# 00_-_Top_Sheet.net
KiCad netlist of a schematic drawn in Altium Designer
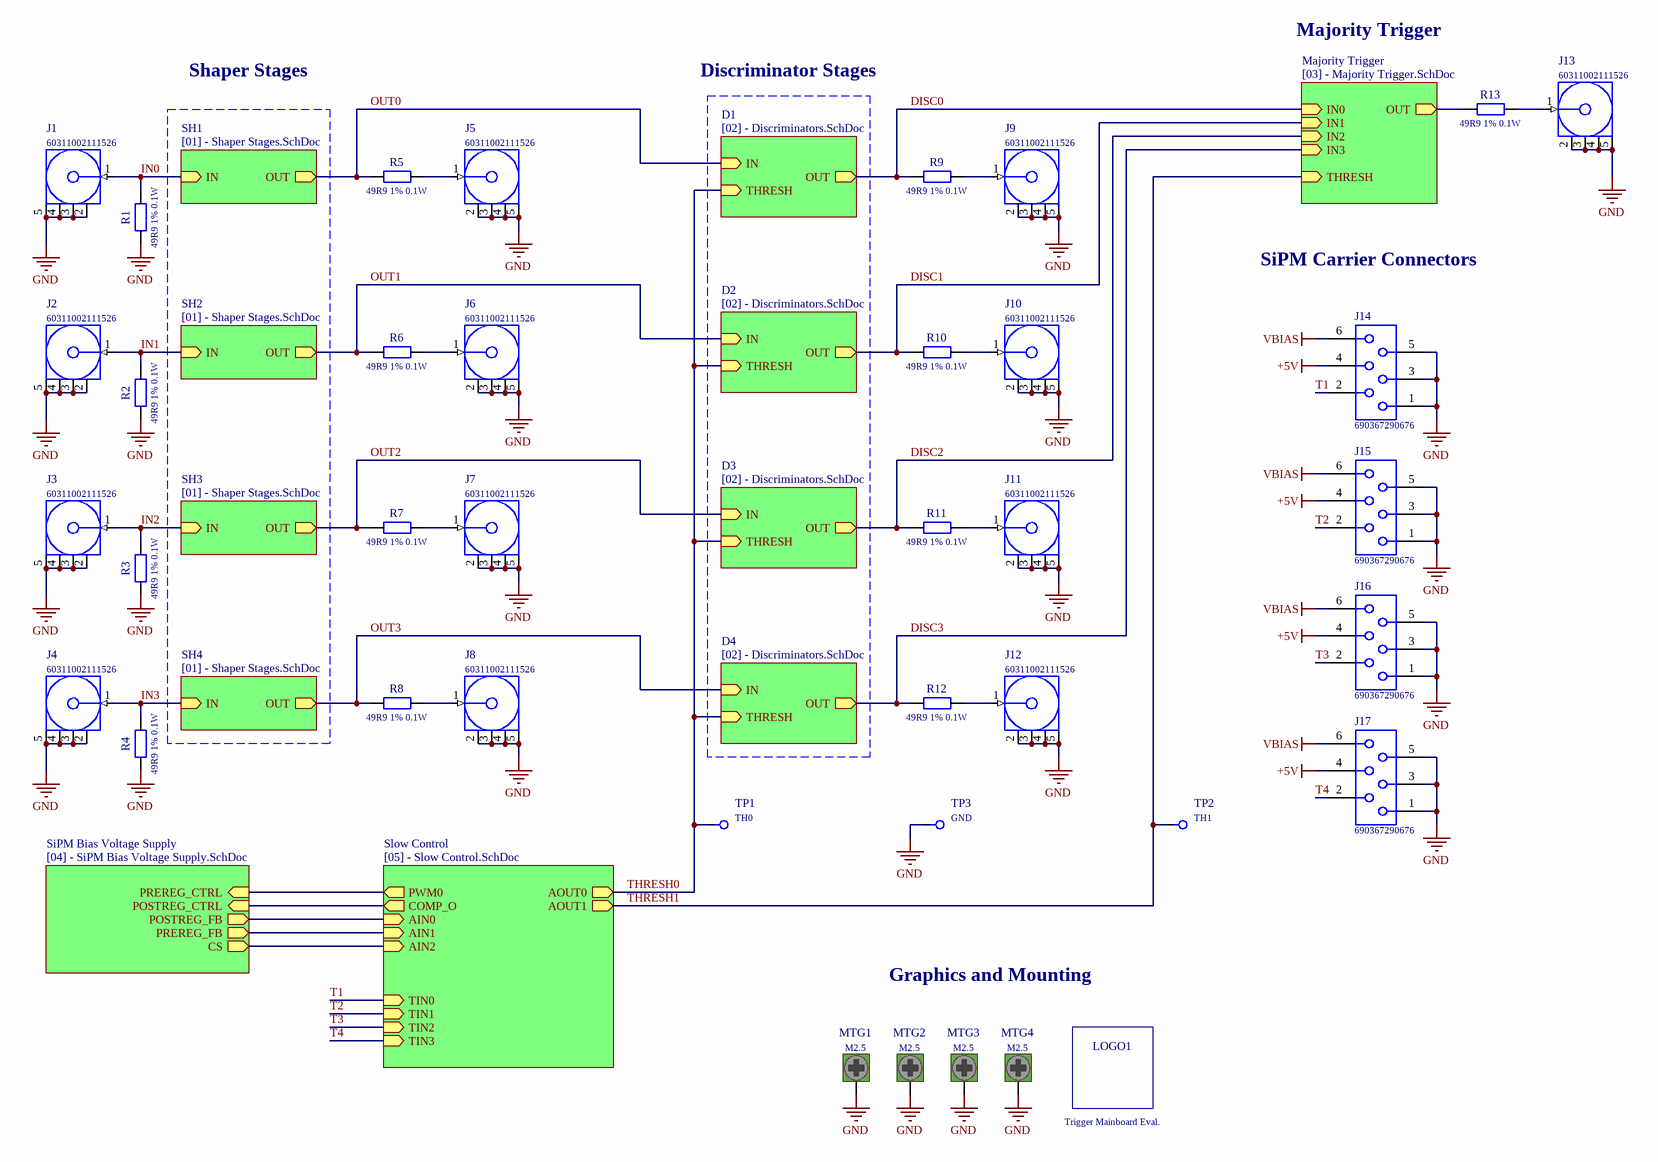
[diagram p0: [00] - Top Sheet.SchDoc]

(export (version "E")
  (design (tool "Eeschema 10.0.6"))
  (components
    (comp (ref "J1")
      (value "60311002111526")
      (footprint "60311002111526")
      (description "WR-SMA PCB Jack, THT, Right Angle")
      (fields (field (name "MANUFACTURER") "Wurth Elektronik"))
      (libsource (lib "WR-SMA") (part "60311002111526"))
    )
    (comp (ref "J2")
      (value "60311002111526")
      (footprint "60311002111526")
      (description "WR-SMA PCB Jack, THT, Right Angle")
      (fields (field (name "MANUFACTURER") "Wurth Elektronik"))
      (libsource (lib "WR-SMA") (part "60311002111526"))
    )
    (comp (ref "J3")
      (value "60311002111526")
      (footprint "60311002111526")
      (description "WR-SMA PCB Jack, THT, Right Angle")
      (fields (field (name "MANUFACTURER") "Wurth Elektronik"))
      (libsource (lib "WR-SMA") (part "60311002111526"))
    )
    (comp (ref "J4")
      (value "60311002111526")
      (footprint "60311002111526")
      (description "WR-SMA PCB Jack, THT, Right Angle")
      (fields (field (name "MANUFACTURER") "Wurth Elektronik"))
      (libsource (lib "WR-SMA") (part "60311002111526"))
    )
    (comp (ref "J5")
      (value "60311002111526")
      (footprint "60311002111526")
      (description "WR-SMA PCB Jack, THT, Right Angle")
      (fields (field (name "MANUFACTURER") "Wurth Elektronik"))
      (libsource (lib "WR-SMA") (part "60311002111526"))
    )
    (comp (ref "J6")
      (value "60311002111526")
      (footprint "60311002111526")
      (description "WR-SMA PCB Jack, THT, Right Angle")
      (fields (field (name "MANUFACTURER") "Wurth Elektronik"))
      (libsource (lib "WR-SMA") (part "60311002111526"))
    )
    (comp (ref "J7")
      (value "60311002111526")
      (footprint "60311002111526")
      (description "WR-SMA PCB Jack, THT, Right Angle")
      (fields (field (name "MANUFACTURER") "Wurth Elektronik"))
      (libsource (lib "WR-SMA") (part "60311002111526"))
    )
    (comp (ref "J8")
      (value "60311002111526")
      (footprint "60311002111526")
      (description "WR-SMA PCB Jack, THT, Right Angle")
      (fields (field (name "MANUFACTURER") "Wurth Elektronik"))
      (libsource (lib "WR-SMA") (part "60311002111526"))
    )
    (comp (ref "J9")
      (value "60311002111526")
      (footprint "60311002111526")
      (description "WR-SMA PCB Jack, THT, Right Angle")
      (fields (field (name "MANUFACTURER") "Wurth Elektronik"))
      (libsource (lib "WR-SMA") (part "60311002111526"))
    )
    (comp (ref "J10")
      (value "60311002111526")
      (footprint "60311002111526")
      (description "WR-SMA PCB Jack, THT, Right Angle")
      (fields (field (name "MANUFACTURER") "Wurth Elektronik"))
      (libsource (lib "WR-SMA") (part "60311002111526"))
    )
    (comp (ref "J11")
      (value "60311002111526")
      (footprint "60311002111526")
      (description "WR-SMA PCB Jack, THT, Right Angle")
      (fields (field (name "MANUFACTURER") "Wurth Elektronik"))
      (libsource (lib "WR-SMA") (part "60311002111526"))
    )
    (comp (ref "J12")
      (value "60311002111526")
      (footprint "60311002111526")
      (description "WR-SMA PCB Jack, THT, Right Angle")
      (fields (field (name "MANUFACTURER") "Wurth Elektronik"))
      (libsource (lib "WR-SMA") (part "60311002111526"))
    )
    (comp (ref "J13")
      (value "60311002111526")
      (footprint "60311002111526")
      (description "WR-SMA PCB Jack, THT, Right Angle")
      (fields (field (name "MANUFACTURER") "Wurth Elektronik"))
      (libsource (lib "WR-SMA") (part "60311002111526"))
    )
    (comp (ref "J14")
      (value "690367290676")
      (footprint "690367290676")
      (description "WR-MM MiniModule Connector, Female, SMT, Vertical, pitch 2.54mm, 6pins")
      (fields (field (name "MANUFACTURER") "Wurth Elektronik"))
      (libsource (lib "WR-MM") (part "690367290676"))
    )
    (comp (ref "J15")
      (value "690367290676")
      (footprint "690367290676")
      (description "WR-MM MiniModule Connector, Female, SMT, Vertical, pitch 2.54mm, 6pins")
      (fields (field (name "MANUFACTURER") "Wurth Elektronik"))
      (libsource (lib "WR-MM") (part "690367290676"))
    )
    (comp (ref "J16")
      (value "690367290676")
      (footprint "690367290676")
      (description "WR-MM MiniModule Connector, Female, SMT, Vertical, pitch 2.54mm, 6pins")
      (fields (field (name "MANUFACTURER") "Wurth Elektronik"))
      (libsource (lib "WR-MM") (part "690367290676"))
    )
    (comp (ref "J17")
      (value "690367290676")
      (footprint "690367290676")
      (description "WR-MM MiniModule Connector, Female, SMT, Vertical, pitch 2.54mm, 6pins")
      (fields (field (name "MANUFACTURER") "Wurth Elektronik"))
      (libsource (lib "WR-MM") (part "690367290676"))
    )
    (comp (ref "LOGO1")
      (value "Trigger Mainboard Eval.")
      (footprint "RWTH_LOGO_4x15MM")
      (description "Logo Spaceholder.")
      (fields (field (name "MANUFACTURER") "RWTH"))
      (libsource (lib "CustomComponents") (part "Logo"))
    )
    (comp (ref "MTG1")
      (value "M2.5")
      (footprint "Mounting_Hole_M2.5")
      (description "Simple mounting hole.")
      (libsource (lib "CustomComponents") (part "Mounting_Hole"))
    )
    (comp (ref "MTG2")
      (value "M2.5")
      (footprint "Mounting_Hole_M2.5")
      (description "Simple mounting hole.")
      (libsource (lib "CustomComponents") (part "Mounting_Hole"))
    )
    (comp (ref "MTG3")
      (value "M2.5")
      (footprint "Mounting_Hole_M2.5")
      (description "Simple mounting hole.")
      (libsource (lib "CustomComponents") (part "Mounting_Hole"))
    )
    (comp (ref "MTG4")
      (value "M2.5")
      (footprint "Mounting_Hole_M2.5")
      (description "Simple mounting hole.")
      (libsource (lib "CustomComponents") (part "Mounting_Hole"))
    )
    (comp (ref "R1")
      (value "49R9 1% 0.1W")
      (footprint "0603_RES")
      (description "Simple generic resistor.")
      (libsource (lib "CustomComponents") (part "Resistor"))
    )
    (comp (ref "R2")
      (value "49R9 1% 0.1W")
      (footprint "0603_RES")
      (description "Simple generic resistor.")
      (libsource (lib "CustomComponents") (part "Resistor"))
    )
    (comp (ref "R3")
      (value "49R9 1% 0.1W")
      (footprint "0603_RES")
      (description "Simple generic resistor.")
      (libsource (lib "CustomComponents") (part "Resistor"))
    )
    (comp (ref "R4")
      (value "49R9 1% 0.1W")
      (footprint "0603_RES")
      (description "Simple generic resistor.")
      (libsource (lib "CustomComponents") (part "Resistor"))
    )
    (comp (ref "R5")
      (value "49R9 1% 0.1W")
      (footprint "0603_RES")
      (description "Simple generic resistor.")
      (libsource (lib "CustomComponents") (part "Resistor"))
    )
    (comp (ref "R6")
      (value "49R9 1% 0.1W")
      (footprint "0603_RES")
      (description "Simple generic resistor.")
      (libsource (lib "CustomComponents") (part "Resistor"))
    )
    (comp (ref "R7")
      (value "49R9 1% 0.1W")
      (footprint "0603_RES")
      (description "Simple generic resistor.")
      (libsource (lib "CustomComponents") (part "Resistor"))
    )
    (comp (ref "R8")
      (value "49R9 1% 0.1W")
      (footprint "0603_RES")
      (description "Simple generic resistor.")
      (libsource (lib "CustomComponents") (part "Resistor"))
    )
    (comp (ref "R9")
      (value "49R9 1% 0.1W")
      (footprint "0603_RES")
      (description "Simple generic resistor.")
      (libsource (lib "CustomComponents") (part "Resistor"))
    )
    (comp (ref "R10")
      (value "49R9 1% 0.1W")
      (footprint "0603_RES")
      (description "Simple generic resistor.")
      (libsource (lib "CustomComponents") (part "Resistor"))
    )
    (comp (ref "R11")
      (value "49R9 1% 0.1W")
      (footprint "0603_RES")
      (description "Simple generic resistor.")
      (libsource (lib "CustomComponents") (part "Resistor"))
    )
    (comp (ref "R12")
      (value "49R9 1% 0.1W")
      (footprint "0603_RES")
      (description "Simple generic resistor.")
      (libsource (lib "CustomComponents") (part "Resistor"))
    )
    (comp (ref "R13")
      (value "49R9 1% 0.1W")
      (footprint "0603_RES")
      (description "Simple generic resistor.")
      (libsource (lib "CustomComponents") (part "Resistor"))
    )
    (comp (ref "TP1")
      (value "TH0")
      (footprint "Testpoint_5002")
      (fields (field (name "MANUFACTURER") "Keystone Electronics") (field (name "PARTNUMBER") "500X"))
      (libsource (lib "CustomComponents") (part "Testpoint"))
    )
    (comp (ref "TP2")
      (value "TH1")
      (footprint "Testpoint_5002")
      (fields (field (name "MANUFACTURER") "Keystone Electronics") (field (name "PARTNUMBER") "500X"))
      (libsource (lib "CustomComponents") (part "Testpoint"))
    )
    (comp (ref "TP3")
      (value "GND")
      (footprint "Testpoint_5001")
      (fields (field (name "MANUFACTURER") "Keystone Electronics") (field (name "PARTNUMBER") "500X"))
      (libsource (lib "CustomComponents") (part "Testpoint"))
    )
  )
  (nets
    (net (code "1") (name "+5V") (class "Default")
      (node (ref "J14") (pin "4") (pinfunction "4_4") (pintype "passive"))
      (node (ref "J15") (pin "4") (pinfunction "4_4") (pintype "passive"))
      (node (ref "J16") (pin "4") (pinfunction "4_4") (pintype "passive"))
      (node (ref "J17") (pin "4") (pinfunction "4_4") (pintype "passive"))
    )
    (net (code "4") (name "/DISC0") (class "Default")
      (node (ref "R9") (pin "2") (pinfunction "2_2") (pintype "passive"))
    )
    (net (code "5") (name "/DISC1") (class "Default")
      (node (ref "R10") (pin "2") (pinfunction "2_2") (pintype "passive"))
    )
    (net (code "6") (name "/DISC2") (class "Default")
      (node (ref "R11") (pin "2") (pinfunction "2_2") (pintype "passive"))
    )
    (net (code "7") (name "/DISC3") (class "Default")
      (node (ref "R12") (pin "2") (pinfunction "2_2") (pintype "passive"))
    )
    (net (code "8") (name "/IN0") (class "Default")
      (node (ref "J1") (pin "1") (pinfunction "Signal_1") (pintype "input"))
      (node (ref "R1") (pin "1") (pinfunction "1_1") (pintype "passive"))
    )
    (net (code "9") (name "/IN1") (class "Default")
      (node (ref "J2") (pin "1") (pinfunction "Signal_1") (pintype "input"))
      (node (ref "R2") (pin "1") (pinfunction "1_1") (pintype "passive"))
    )
    (net (code "10") (name "/IN2") (class "Default")
      (node (ref "J3") (pin "1") (pinfunction "Signal_1") (pintype "input"))
      (node (ref "R3") (pin "1") (pinfunction "1_1") (pintype "passive"))
    )
    (net (code "11") (name "/IN3") (class "Default")
      (node (ref "J4") (pin "1") (pinfunction "Signal_1") (pintype "input"))
      (node (ref "R4") (pin "1") (pinfunction "1_1") (pintype "passive"))
    )
    (net (code "12") (name "/OUT") (class "Default")
      (node (ref "R13") (pin "2") (pinfunction "2_2") (pintype "passive"))
    )
    (net (code "13") (name "/OUT0") (class "Default")
      (node (ref "R5") (pin "2") (pinfunction "2_2") (pintype "passive"))
    )
    (net (code "14") (name "/OUT1") (class "Default")
      (node (ref "R6") (pin "2") (pinfunction "2_2") (pintype "passive"))
    )
    (net (code "15") (name "/OUT2") (class "Default")
      (node (ref "R7") (pin "2") (pinfunction "2_2") (pintype "passive"))
    )
    (net (code "16") (name "/OUT3") (class "Default")
      (node (ref "R8") (pin "2") (pinfunction "2_2") (pintype "passive"))
    )
    (net (code "20") (name "/T1") (class "Default")
      (node (ref "J14") (pin "2") (pinfunction "2_2") (pintype "passive"))
    )
    (net (code "21") (name "/T2") (class "Default")
      (node (ref "J15") (pin "2") (pinfunction "2_2") (pintype "passive"))
    )
    (net (code "22") (name "/T3") (class "Default")
      (node (ref "J16") (pin "2") (pinfunction "2_2") (pintype "passive"))
    )
    (net (code "23") (name "/T4") (class "Default")
      (node (ref "J17") (pin "2") (pinfunction "2_2") (pintype "passive"))
    )
    (net (code "24") (name "/THRESH0") (class "Default")
      (node (ref "TP1") (pin "1") (pinfunction "1_1") (pintype "passive"))
    )
    (net (code "25") (name "/THRESH1") (class "Default")
      (node (ref "TP2") (pin "1") (pinfunction "1_1") (pintype "passive"))
    )
    (net (code "26") (name "GND") (class "Default")
      (node (ref "J1") (pin "2") (pinfunction "GND_2") (pintype "power_in"))
      (node (ref "J1") (pin "3") (pinfunction "GND_3") (pintype "power_in"))
      (node (ref "J1") (pin "4") (pinfunction "GND_4") (pintype "power_in"))
      (node (ref "J1") (pin "5") (pinfunction "GND_5") (pintype "power_in"))
      (node (ref "J10") (pin "2") (pinfunction "GND_2") (pintype "power_in"))
      (node (ref "J10") (pin "3") (pinfunction "GND_3") (pintype "power_in"))
      (node (ref "J10") (pin "4") (pinfunction "GND_4") (pintype "power_in"))
      (node (ref "J10") (pin "5") (pinfunction "GND_5") (pintype "power_in"))
      (node (ref "J11") (pin "2") (pinfunction "GND_2") (pintype "power_in"))
      (node (ref "J11") (pin "3") (pinfunction "GND_3") (pintype "power_in"))
      (node (ref "J11") (pin "4") (pinfunction "GND_4") (pintype "power_in"))
      (node (ref "J11") (pin "5") (pinfunction "GND_5") (pintype "power_in"))
      (node (ref "J12") (pin "2") (pinfunction "GND_2") (pintype "power_in"))
      (node (ref "J12") (pin "3") (pinfunction "GND_3") (pintype "power_in"))
      (node (ref "J12") (pin "4") (pinfunction "GND_4") (pintype "power_in"))
      (node (ref "J12") (pin "5") (pinfunction "GND_5") (pintype "power_in"))
      (node (ref "J13") (pin "2") (pinfunction "GND_2") (pintype "power_in"))
      (node (ref "J13") (pin "3") (pinfunction "GND_3") (pintype "power_in"))
      (node (ref "J13") (pin "4") (pinfunction "GND_4") (pintype "power_in"))
      (node (ref "J13") (pin "5") (pinfunction "GND_5") (pintype "power_in"))
      (node (ref "J14") (pin "1") (pinfunction "1_1") (pintype "passive"))
      (node (ref "J14") (pin "3") (pinfunction "3_3") (pintype "passive"))
      (node (ref "J14") (pin "5") (pinfunction "5_5") (pintype "passive"))
      (node (ref "J15") (pin "1") (pinfunction "1_1") (pintype "passive"))
      (node (ref "J15") (pin "3") (pinfunction "3_3") (pintype "passive"))
      (node (ref "J15") (pin "5") (pinfunction "5_5") (pintype "passive"))
      (node (ref "J16") (pin "1") (pinfunction "1_1") (pintype "passive"))
      (node (ref "J16") (pin "3") (pinfunction "3_3") (pintype "passive"))
      (node (ref "J16") (pin "5") (pinfunction "5_5") (pintype "passive"))
      (node (ref "J17") (pin "1") (pinfunction "1_1") (pintype "passive"))
      (node (ref "J17") (pin "3") (pinfunction "3_3") (pintype "passive"))
      (node (ref "J17") (pin "5") (pinfunction "5_5") (pintype "passive"))
      (node (ref "J2") (pin "2") (pinfunction "GND_2") (pintype "power_in"))
      (node (ref "J2") (pin "3") (pinfunction "GND_3") (pintype "power_in"))
      (node (ref "J2") (pin "4") (pinfunction "GND_4") (pintype "power_in"))
      (node (ref "J2") (pin "5") (pinfunction "GND_5") (pintype "power_in"))
      (node (ref "J3") (pin "2") (pinfunction "GND_2") (pintype "power_in"))
      (node (ref "J3") (pin "3") (pinfunction "GND_3") (pintype "power_in"))
      (node (ref "J3") (pin "4") (pinfunction "GND_4") (pintype "power_in"))
      (node (ref "J3") (pin "5") (pinfunction "GND_5") (pintype "power_in"))
      (node (ref "J4") (pin "2") (pinfunction "GND_2") (pintype "power_in"))
      (node (ref "J4") (pin "3") (pinfunction "GND_3") (pintype "power_in"))
      (node (ref "J4") (pin "4") (pinfunction "GND_4") (pintype "power_in"))
      (node (ref "J4") (pin "5") (pinfunction "GND_5") (pintype "power_in"))
      (node (ref "J5") (pin "2") (pinfunction "GND_2") (pintype "power_in"))
      (node (ref "J5") (pin "3") (pinfunction "GND_3") (pintype "power_in"))
      (node (ref "J5") (pin "4") (pinfunction "GND_4") (pintype "power_in"))
      (node (ref "J5") (pin "5") (pinfunction "GND_5") (pintype "power_in"))
      (node (ref "J6") (pin "2") (pinfunction "GND_2") (pintype "power_in"))
      (node (ref "J6") (pin "3") (pinfunction "GND_3") (pintype "power_in"))
      (node (ref "J6") (pin "4") (pinfunction "GND_4") (pintype "power_in"))
      (node (ref "J6") (pin "5") (pinfunction "GND_5") (pintype "power_in"))
      (node (ref "J7") (pin "2") (pinfunction "GND_2") (pintype "power_in"))
      (node (ref "J7") (pin "3") (pinfunction "GND_3") (pintype "power_in"))
      (node (ref "J7") (pin "4") (pinfunction "GND_4") (pintype "power_in"))
      (node (ref "J7") (pin "5") (pinfunction "GND_5") (pintype "power_in"))
      (node (ref "J8") (pin "2") (pinfunction "GND_2") (pintype "power_in"))
      (node (ref "J8") (pin "3") (pinfunction "GND_3") (pintype "power_in"))
      (node (ref "J8") (pin "4") (pinfunction "GND_4") (pintype "power_in"))
      (node (ref "J8") (pin "5") (pinfunction "GND_5") (pintype "power_in"))
      (node (ref "J9") (pin "2") (pinfunction "GND_2") (pintype "power_in"))
      (node (ref "J9") (pin "3") (pinfunction "GND_3") (pintype "power_in"))
      (node (ref "J9") (pin "4") (pinfunction "GND_4") (pintype "power_in"))
      (node (ref "J9") (pin "5") (pinfunction "GND_5") (pintype "power_in"))
      (node (ref "MTG1") (pin "1") (pinfunction "1_1") (pintype "passive"))
      (node (ref "MTG2") (pin "1") (pinfunction "1_1") (pintype "passive"))
      (node (ref "MTG3") (pin "1") (pinfunction "1_1") (pintype "passive"))
      (node (ref "MTG4") (pin "1") (pinfunction "1_1") (pintype "passive"))
      (node (ref "R1") (pin "2") (pinfunction "2_2") (pintype "passive"))
      (node (ref "R2") (pin "2") (pinfunction "2_2") (pintype "passive"))
      (node (ref "R3") (pin "2") (pinfunction "2_2") (pintype "passive"))
      (node (ref "R4") (pin "2") (pinfunction "2_2") (pintype "passive"))
      (node (ref "TP3") (pin "1") (pinfunction "1_1") (pintype "passive"))
    )
    (net (code "27") (name "Net-(J5-Signal)") (class "Default")
      (node (ref "J5") (pin "1") (pinfunction "Signal_1") (pintype "input"))
      (node (ref "R5") (pin "1") (pinfunction "1_1") (pintype "passive"))
    )
    (net (code "28") (name "Net-(J6-Signal)") (class "Default")
      (node (ref "J6") (pin "1") (pinfunction "Signal_1") (pintype "input"))
      (node (ref "R6") (pin "1") (pinfunction "1_1") (pintype "passive"))
    )
    (net (code "29") (name "Net-(J7-Signal)") (class "Default")
      (node (ref "J7") (pin "1") (pinfunction "Signal_1") (pintype "input"))
      (node (ref "R7") (pin "1") (pinfunction "1_1") (pintype "passive"))
    )
    (net (code "30") (name "Net-(J8-Signal)") (class "Default")
      (node (ref "J8") (pin "1") (pinfunction "Signal_1") (pintype "input"))
      (node (ref "R8") (pin "1") (pinfunction "1_1") (pintype "passive"))
    )
    (net (code "31") (name "Net-(J9-Signal)") (class "Default")
      (node (ref "J9") (pin "1") (pinfunction "Signal_1") (pintype "input"))
      (node (ref "R9") (pin "1") (pinfunction "1_1") (pintype "passive"))
    )
    (net (code "32") (name "Net-(J10-Signal)") (class "Default")
      (node (ref "J10") (pin "1") (pinfunction "Signal_1") (pintype "input"))
      (node (ref "R10") (pin "1") (pinfunction "1_1") (pintype "passive"))
    )
    (net (code "33") (name "Net-(J11-Signal)") (class "Default")
      (node (ref "J11") (pin "1") (pinfunction "Signal_1") (pintype "input"))
      (node (ref "R11") (pin "1") (pinfunction "1_1") (pintype "passive"))
    )
    (net (code "34") (name "Net-(J12-Signal)") (class "Default")
      (node (ref "J12") (pin "1") (pinfunction "Signal_1") (pintype "input"))
      (node (ref "R12") (pin "1") (pinfunction "1_1") (pintype "passive"))
    )
    (net (code "35") (name "Net-(J13-Signal)") (class "Default")
      (node (ref "J13") (pin "1") (pinfunction "Signal_1") (pintype "input"))
      (node (ref "R13") (pin "1") (pinfunction "1_1") (pintype "passive"))
    )
    (net (code "36") (name "VBIAS") (class "Default")
      (node (ref "J14") (pin "6") (pinfunction "6_6") (pintype "passive"))
      (node (ref "J15") (pin "6") (pinfunction "6_6") (pintype "passive"))
      (node (ref "J16") (pin "6") (pinfunction "6_6") (pintype "passive"))
      (node (ref "J17") (pin "6") (pinfunction "6_6") (pintype "passive"))
    )
  )
)
